# orajel.net
KiCad netlist of a schematic drawn in EAGLE
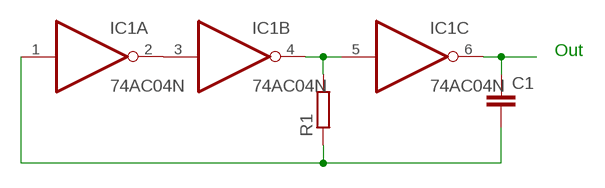
[diagram p0: schematic, sheet 1]

(export (version "E")
  (design (tool "Eeschema 10.0.6"))
  (components
    (comp (ref "C1")
      (value "C-EU025-030X050")
      (footprint "eagle-import:C025-030X050")
      (libsource (lib "eagle-import") (part "C-EU025-030X050"))
    )
    (comp (ref "IC1")
      (value "74AC04N")
      (footprint "eagle-import:DIL14")
      (libsource (lib "eagle-import") (part "7404NAC"))
    )
    (comp (ref "R1")
      (value "R-EU_0207/12")
      (footprint "eagle-import:0207_12")
      (libsource (lib "eagle-import") (part "R-EU_0207/12"))
    )
  )
  (nets
    (net (code "1") (name "Net-(IC1A-I)") (class "Default")
      (node (ref "C1") (pin "2") (pinfunction "2_2") (pintype "passive"))
      (node (ref "IC1") (pin "1") (pinfunction "I_1") (pintype "input"))
      (node (ref "R1") (pin "1") (pinfunction "1_1") (pintype "passive"))
    )
    (net (code "2") (name "Net-(IC1A-O)") (class "Default")
      (node (ref "IC1") (pin "2") (pinfunction "O_2") (pintype "output"))
      (node (ref "IC1") (pin "3") (pinfunction "I_3") (pintype "input"))
    )
    (net (code "3") (name "Net-(IC1B-O)") (class "Default")
      (node (ref "IC1") (pin "4") (pinfunction "O_4") (pintype "output"))
      (node (ref "IC1") (pin "5") (pinfunction "I_5") (pintype "input"))
      (node (ref "R1") (pin "2") (pinfunction "2_2") (pintype "passive"))
    )
    (net (code "4") (name "Net-(IC1C-O)") (class "Default")
      (node (ref "C1") (pin "1") (pinfunction "1_1") (pintype "passive"))
      (node (ref "IC1") (pin "6") (pinfunction "O_6") (pintype "output"))
    )
  )
)
